# LAN9252-2.net
KiCad netlist of a schematic drawn in Altium Designer
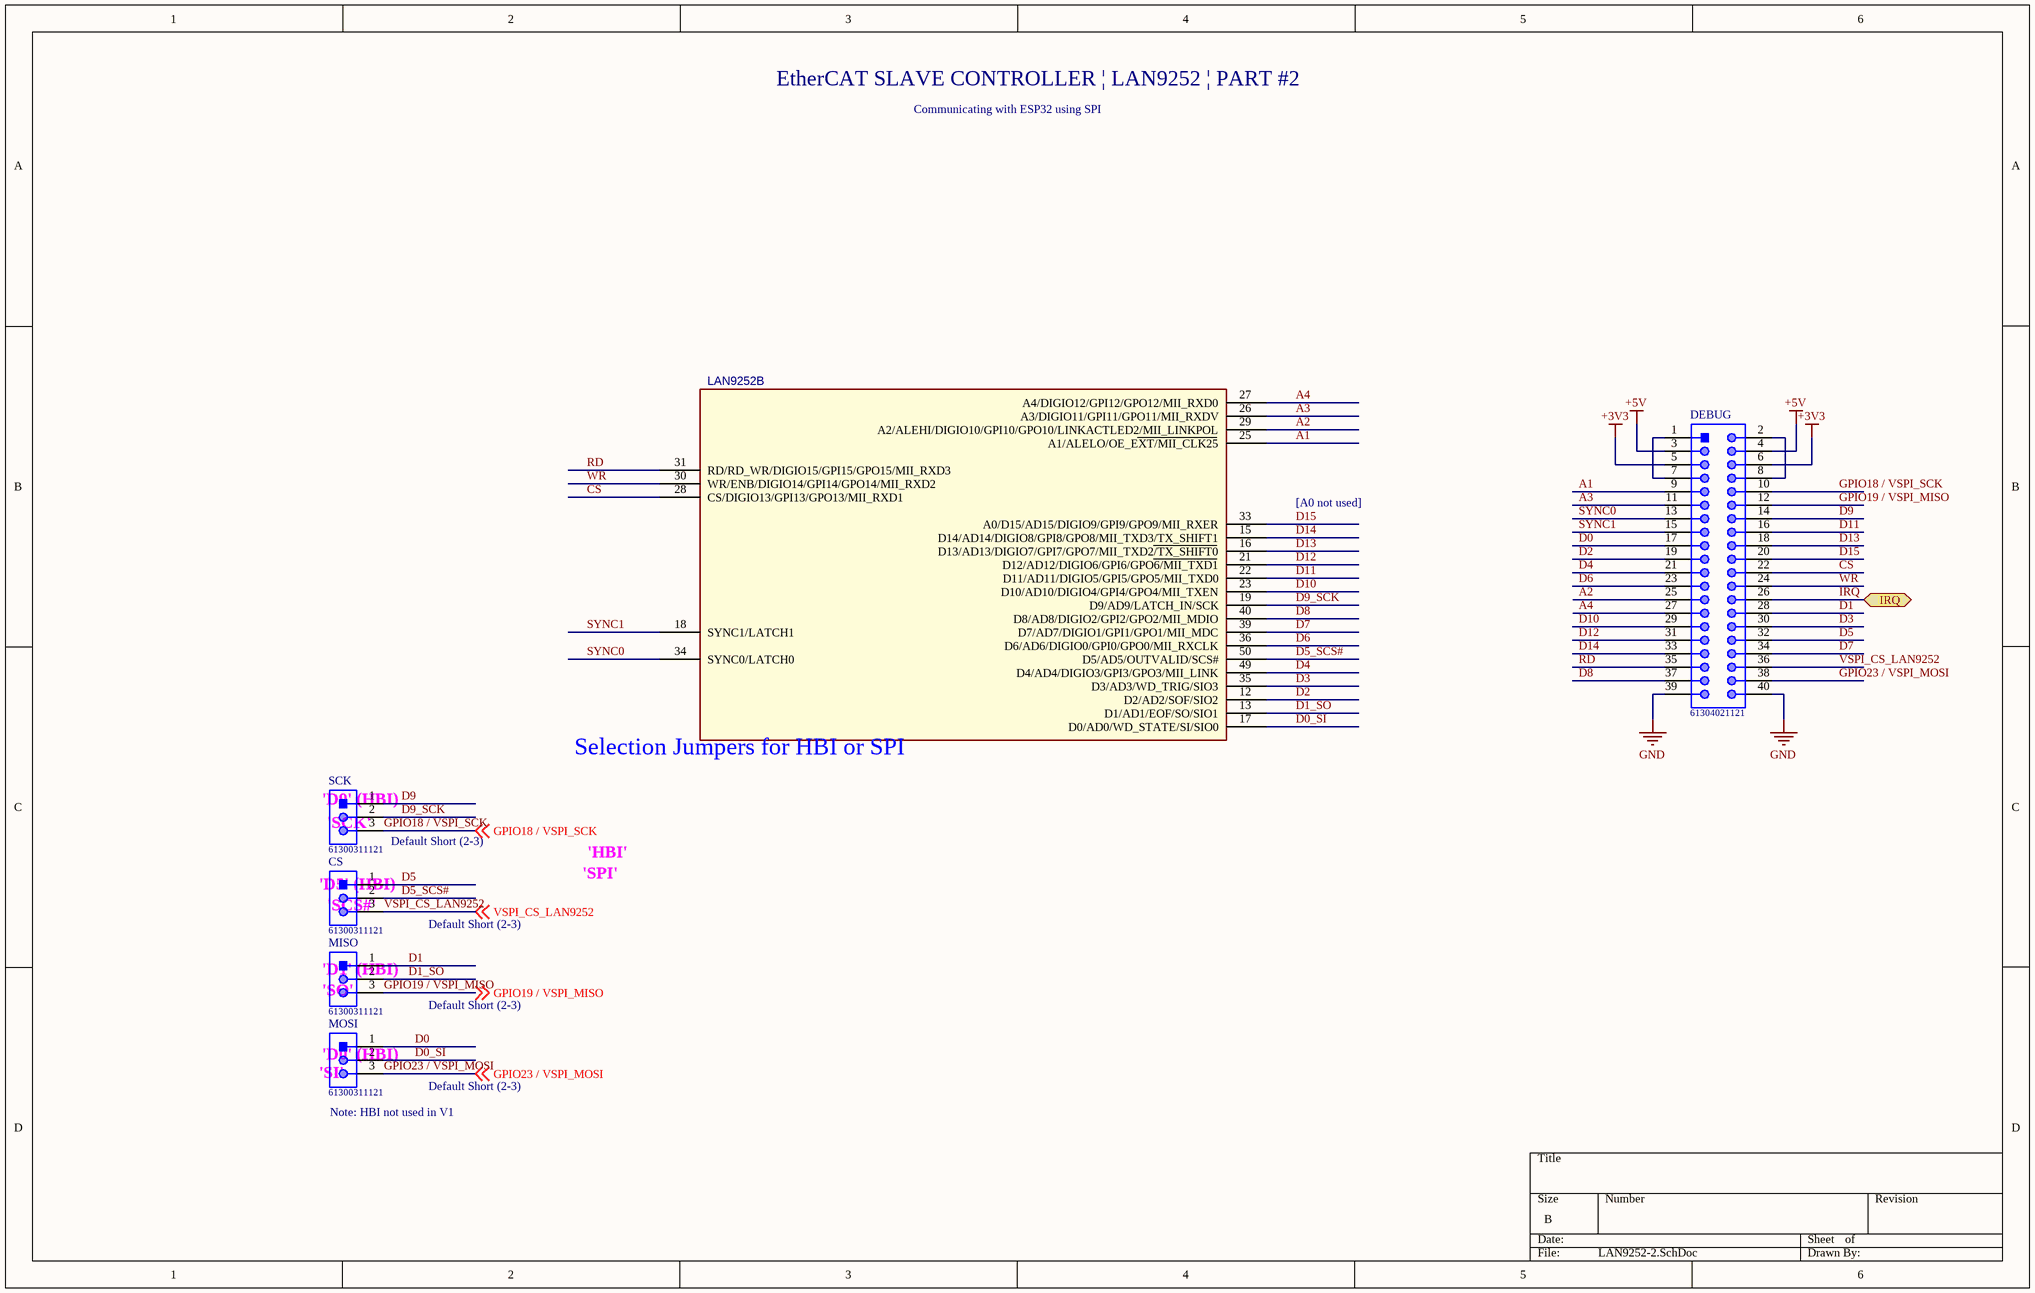
[diagram p0: LAN9252-2.SchDoc]

(export (version "E")
  (design (tool "Eeschema 10.0.6"))
  (components
    (comp (ref "CS")
      (value "61300311121")
      (footprint "61300311121")
      (description "THT Vertical Pin Header WR-PHD, Pitch 2.54 mm, Single Row, 3 pins")
      (fields (field (name "MANUFACTURER") "Wurth Elektronik") (field (name "PUBLISHER") "WurthElektronik"))
      (libsource (lib "Altium Content Vault") (part "WE-CN-1P-M-R3"))
    )
    (comp (ref "DEBUG")
      (value "61304021121")
      (footprint "61304021121")
      (description "THT Vertical Pin Header WR-PHD, Pitch 2.54 mm, Dual Row, 40 pins")
      (fields (field (name "MANUFACTURER") "Wurth Elektronik") (field (name "PUBLISHER") "WurthElektronik"))
      (libsource (lib "Altium Content Vault") (part "WE-CN-2P-M-R40"))
    )
    (comp (ref "LAN9252")
      (value "~")
      (footprint "LAN9252_QFN")
      (description "IC, 2/3-Port EtherCAT® Slave Controller, QFN64")
      (fields (field (name "OWNER") "Manikandan"))
      (libsource (lib "UNG_UNG") (part "LAN9252_QFN64"))
    )
    (comp (ref "MISO")
      (value "61300311121")
      (footprint "61300311121")
      (description "THT Vertical Pin Header WR-PHD, Pitch 2.54 mm, Single Row, 3 pins")
      (fields (field (name "MANUFACTURER") "Wurth Elektronik") (field (name "PUBLISHER") "WurthElektronik"))
      (libsource (lib "Altium Content Vault") (part "WE-CN-1P-M-R3"))
    )
    (comp (ref "MOSI")
      (value "61300311121")
      (footprint "61300311121")
      (description "THT Vertical Pin Header WR-PHD, Pitch 2.54 mm, Single Row, 3 pins")
      (fields (field (name "MANUFACTURER") "Wurth Elektronik") (field (name "PUBLISHER") "WurthElektronik"))
      (libsource (lib "Altium Content Vault") (part "WE-CN-1P-M-R3"))
    )
    (comp (ref "SCK")
      (value "61300311121")
      (footprint "61300311121")
      (description "THT Vertical Pin Header WR-PHD, Pitch 2.54 mm, Single Row, 3 pins")
      (fields (field (name "MANUFACTURER") "Wurth Elektronik") (field (name "PUBLISHER") "WurthElektronik"))
      (libsource (lib "Altium Content Vault") (part "WE-CN-1P-M-R3"))
    )
  )
  (nets
    (net (code "1") (name "+3V3") (class "Default")
      (node (ref "DEBUG") (pin "5") (pinfunction "5_5") (pintype "passive"))
      (node (ref "DEBUG") (pin "6") (pinfunction "6_6") (pintype "passive"))
    )
    (net (code "2") (name "+5V") (class "Default")
      (node (ref "DEBUG") (pin "3") (pinfunction "3_3") (pintype "passive"))
      (node (ref "DEBUG") (pin "4") (pinfunction "4_4") (pintype "passive"))
    )
    (net (code "3") (name "/A1") (class "Default")
      (node (ref "DEBUG") (pin "9") (pinfunction "9_9") (pintype "passive"))
      (node (ref "LAN9252") (pin "25") (pinfunction "A1/ALELO/OE_EXT/MII_CLK25_25") (pintype "passive"))
    )
    (net (code "4") (name "/A2") (class "Default")
      (node (ref "DEBUG") (pin "25") (pinfunction "25_25") (pintype "passive"))
      (node (ref "LAN9252") (pin "29") (pinfunction "A2/ALEHI/DIGIO10/GPI10/GPO10/LINKACTLED2/MII_LINKPOL_29") (pintype "passive"))
    )
    (net (code "5") (name "/A3") (class "Default")
      (node (ref "DEBUG") (pin "11") (pinfunction "11_11") (pintype "passive"))
      (node (ref "LAN9252") (pin "26") (pinfunction "A3/DIGIO11/GPI11/GPO11/MII_RXDV_26") (pintype "passive"))
    )
    (net (code "6") (name "/A4") (class "Default")
      (node (ref "DEBUG") (pin "27") (pinfunction "27_27") (pintype "passive"))
      (node (ref "LAN9252") (pin "27") (pinfunction "A4/DIGIO12/GPI12/GPO12/MII_RXD0_27") (pintype "passive"))
    )
    (net (code "7") (name "/CS") (class "Default")
      (node (ref "DEBUG") (pin "22") (pinfunction "22_22") (pintype "passive"))
      (node (ref "LAN9252") (pin "28") (pinfunction "CS/DIGIO13/GPI13/GPO13/MII_RXD1_28") (pintype "passive"))
    )
    (net (code "8") (name "/D0") (class "Default")
      (node (ref "DEBUG") (pin "17") (pinfunction "17_17") (pintype "passive"))
      (node (ref "MOSI") (pin "1") (pinfunction "1_1") (pintype "passive"))
    )
    (net (code "9") (name "/D0_SI") (class "Default")
      (node (ref "LAN9252") (pin "17") (pinfunction "D0/AD0/WD_STATE/SI/SIO0_17") (pintype "passive"))
      (node (ref "MOSI") (pin "2") (pinfunction "2_2") (pintype "passive"))
    )
    (net (code "10") (name "/D1") (class "Default")
      (node (ref "DEBUG") (pin "28") (pinfunction "28_28") (pintype "passive"))
      (node (ref "MISO") (pin "1") (pinfunction "1_1") (pintype "passive"))
    )
    (net (code "11") (name "/D1_SO") (class "Default")
      (node (ref "LAN9252") (pin "13") (pinfunction "D1/AD1/EOF/SO/SIO1_13") (pintype "passive"))
      (node (ref "MISO") (pin "2") (pinfunction "2_2") (pintype "passive"))
    )
    (net (code "12") (name "/D2") (class "Default")
      (node (ref "DEBUG") (pin "19") (pinfunction "19_19") (pintype "passive"))
      (node (ref "LAN9252") (pin "12") (pinfunction "D2/AD2/SOF/SIO2_12") (pintype "passive"))
    )
    (net (code "13") (name "/D3") (class "Default")
      (node (ref "DEBUG") (pin "30") (pinfunction "30_30") (pintype "passive"))
      (node (ref "LAN9252") (pin "35") (pinfunction "D3/AD3/WD_TRIG/SIO3_35") (pintype "passive"))
    )
    (net (code "14") (name "/D4") (class "Default")
      (node (ref "DEBUG") (pin "21") (pinfunction "21_21") (pintype "passive"))
      (node (ref "LAN9252") (pin "49") (pinfunction "D4/AD4/DIGIO3/GPI3/GPO3/MII_LINK_49") (pintype "passive"))
    )
    (net (code "15") (name "/D5") (class "Default")
      (node (ref "CS") (pin "1") (pinfunction "1_1") (pintype "passive"))
      (node (ref "DEBUG") (pin "32") (pinfunction "32_32") (pintype "passive"))
    )
    (net (code "16") (name "/D5_SCS#") (class "Default")
      (node (ref "CS") (pin "2") (pinfunction "2_2") (pintype "passive"))
      (node (ref "LAN9252") (pin "50") (pinfunction "D5/AD5/OUTVALID/SCS#_50") (pintype "passive"))
    )
    (net (code "17") (name "/D6") (class "Default")
      (node (ref "DEBUG") (pin "23") (pinfunction "23_23") (pintype "passive"))
      (node (ref "LAN9252") (pin "36") (pinfunction "D6/AD6/DIGIO0/GPI0/GPO0/MII_RXCLK_36") (pintype "passive"))
    )
    (net (code "18") (name "/D7") (class "Default")
      (node (ref "DEBUG") (pin "34") (pinfunction "34_34") (pintype "passive"))
      (node (ref "LAN9252") (pin "39") (pinfunction "D7/AD7/DIGIO1/GPI1/GPO1/MII_MDC_39") (pintype "passive"))
    )
    (net (code "19") (name "/D8") (class "Default")
      (node (ref "DEBUG") (pin "37") (pinfunction "37_37") (pintype "passive"))
      (node (ref "LAN9252") (pin "40") (pinfunction "D8/AD8/DIGIO2/GPI2/GPO2/MII_MDIO_40") (pintype "passive"))
    )
    (net (code "20") (name "/D9") (class "Default")
      (node (ref "DEBUG") (pin "14") (pinfunction "14_14") (pintype "passive"))
      (node (ref "SCK") (pin "1") (pinfunction "1_1") (pintype "passive"))
    )
    (net (code "21") (name "/D9_SCK") (class "Default")
      (node (ref "LAN9252") (pin "19") (pinfunction "D9/AD9/LATCH_IN/SCK_19") (pintype "passive"))
      (node (ref "SCK") (pin "2") (pinfunction "2_2") (pintype "passive"))
    )
    (net (code "22") (name "/D10") (class "Default")
      (node (ref "DEBUG") (pin "29") (pinfunction "29_29") (pintype "passive"))
      (node (ref "LAN9252") (pin "23") (pinfunction "D10/AD10/DIGIO4/GPI4/GPO4/MII_TXEN_23") (pintype "passive"))
    )
    (net (code "23") (name "/D11") (class "Default")
      (node (ref "DEBUG") (pin "16") (pinfunction "16_16") (pintype "passive"))
      (node (ref "LAN9252") (pin "22") (pinfunction "D11/AD11/DIGIO5/GPI5/GPO5/MII_TXD0_22") (pintype "passive"))
    )
    (net (code "24") (name "/D12") (class "Default")
      (node (ref "DEBUG") (pin "31") (pinfunction "31_31") (pintype "passive"))
      (node (ref "LAN9252") (pin "21") (pinfunction "D12/AD12/DIGIO6/GPI6/GPO6/MII_TXD1_21") (pintype "passive"))
    )
    (net (code "25") (name "/D13") (class "Default")
      (node (ref "DEBUG") (pin "18") (pinfunction "18_18") (pintype "passive"))
      (node (ref "LAN9252") (pin "16") (pinfunction "D13/AD13/DIGIO7/GPI7/GPO7/MII_TXD2/TX_SHIFT0_16") (pintype "passive"))
    )
    (net (code "26") (name "/D14") (class "Default")
      (node (ref "DEBUG") (pin "33") (pinfunction "33_33") (pintype "passive"))
      (node (ref "LAN9252") (pin "15") (pinfunction "D14/AD14/DIGIO8/GPI8/GPO8/MII_TXD3/TX_SHIFT1_15") (pintype "passive"))
    )
    (net (code "27") (name "/D15") (class "Default")
      (node (ref "DEBUG") (pin "20") (pinfunction "20_20") (pintype "passive"))
      (node (ref "LAN9252") (pin "33") (pinfunction "A0/D15/AD15/DIGIO9/GPI9/GPO9/MII_RXER_33") (pintype "passive"))
    )
    (net (code "28") (name "/IRQ") (class "Default")
      (node (ref "DEBUG") (pin "26") (pinfunction "26_26") (pintype "passive"))
    )
    (net (code "29") (name "/RD") (class "Default")
      (node (ref "DEBUG") (pin "35") (pinfunction "35_35") (pintype "passive"))
      (node (ref "LAN9252") (pin "31") (pinfunction "RD/RD_WR/DIGIO15/GPI15/GPO15/MII_RXD3_31") (pintype "passive"))
    )
    (net (code "30") (name "/SYNC0") (class "Default")
      (node (ref "DEBUG") (pin "13") (pinfunction "13_13") (pintype "passive"))
      (node (ref "LAN9252") (pin "34") (pinfunction "SYNC0/LATCH0_34") (pintype "passive"))
    )
    (net (code "31") (name "/SYNC1") (class "Default")
      (node (ref "DEBUG") (pin "15") (pinfunction "15_15") (pintype "passive"))
      (node (ref "LAN9252") (pin "18") (pinfunction "SYNC1/LATCH1_18") (pintype "passive"))
    )
    (net (code "32") (name "/WR") (class "Default")
      (node (ref "DEBUG") (pin "24") (pinfunction "24_24") (pintype "passive"))
      (node (ref "LAN9252") (pin "30") (pinfunction "WR/ENB/DIGIO14/GPI14/GPO14/MII_RXD2_30") (pintype "passive"))
    )
    (net (code "33") (name "GND") (class "Default")
      (node (ref "DEBUG") (pin "39") (pinfunction "39_39") (pintype "passive"))
      (node (ref "DEBUG") (pin "40") (pinfunction "40_40") (pintype "passive"))
    )
    (net (code "34") (name "GPIO18 {slash} VSPI_SCK") (class "Default")
      (node (ref "DEBUG") (pin "10") (pinfunction "10_10") (pintype "passive"))
      (node (ref "SCK") (pin "3") (pinfunction "3_3") (pintype "passive"))
    )
    (net (code "35") (name "GPIO19 {slash} VSPI_MISO") (class "Default")
      (node (ref "DEBUG") (pin "12") (pinfunction "12_12") (pintype "passive"))
      (node (ref "MISO") (pin "3") (pinfunction "3_3") (pintype "passive"))
    )
    (net (code "36") (name "GPIO23 {slash} VSPI_MOSI") (class "Default")
      (node (ref "DEBUG") (pin "38") (pinfunction "38_38") (pintype "passive"))
      (node (ref "MOSI") (pin "3") (pinfunction "3_3") (pintype "passive"))
    )
    (net (code "37") (name "Net-(DEBUG-Pad1)") (class "Default")
      (node (ref "DEBUG") (pin "1") (pinfunction "1_1") (pintype "passive"))
      (node (ref "DEBUG") (pin "7") (pinfunction "7_7") (pintype "passive"))
    )
    (net (code "38") (name "Net-(DEBUG-Pad2)") (class "Default")
      (node (ref "DEBUG") (pin "2") (pinfunction "2_2") (pintype "passive"))
      (node (ref "DEBUG") (pin "8") (pinfunction "8_8") (pintype "passive"))
    )
    (net (code "39") (name "VSPI_CS_LAN9252") (class "Default")
      (node (ref "CS") (pin "3") (pinfunction "3_3") (pintype "passive"))
      (node (ref "DEBUG") (pin "36") (pinfunction "36_36") (pintype "passive"))
    )
  )
)
